# Boost_Converter.net
KiCad netlist of a schematic drawn in Altium Designer
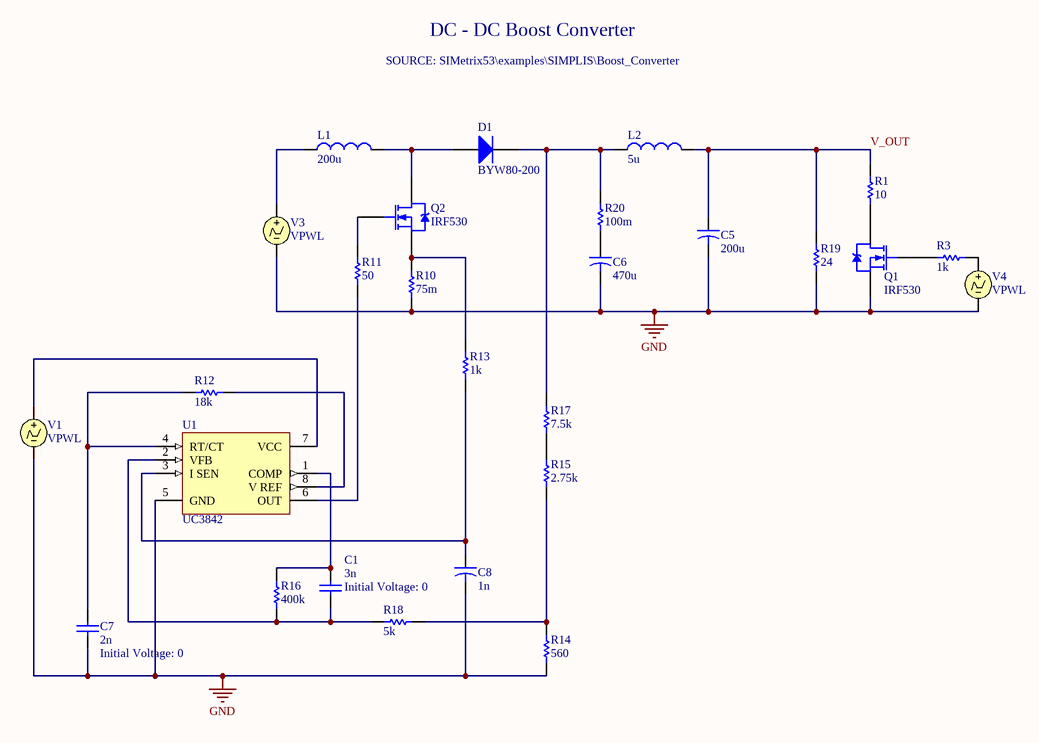
[diagram p0: Boost Converter.SchDoc]

(export (version "E")
  (design (tool "Eeschema 10.0.6"))
  (components
    (comp (ref "C1")
      (value "3n")
      (footprint "RAD-0.3")
      (description "Capacitor")
      (fields
        (field (name "INITIAL VOLTAGE") "0")
        (field (name "Comment") "Cap")
        (field (name "PUBLISHER") "Altium Limited")
      )
      (libsource (lib "Miscellaneous Devices") (part "Cap"))
    )
    (comp (ref "C5")
      (value "Cap Elec (L1-3)")
      (footprint "CAPR5-4X5")
      (description "Electrolytic Capacitor (Levels 1-3)")
      (fields (field (name "CC") "200u") (field (name "PUBLISHER") "Altium Limited"))
      (libsource (lib "SIMetrix Devices") (part "Cap Elec (L1-3)"))
    )
    (comp (ref "C6")
      (value "Cap Elec (L1-3)")
      (footprint "CAPR5-4X5")
      (description "Electrolytic Capacitor (Levels 1-3)")
      (fields (field (name "CC") "470u") (field (name "PUBLISHER") "Altium Limited"))
      (libsource (lib "SIMetrix Devices") (part "Cap Elec (L1-3)"))
    )
    (comp (ref "C7")
      (value "2n")
      (footprint "RAD-0.3")
      (description "Capacitor")
      (fields
        (field (name "INITIAL VOLTAGE") "0")
        (field (name "Comment") "Cap")
        (field (name "PUBLISHER") "Altium Limited")
      )
      (libsource (lib "Miscellaneous Devices") (part "Cap"))
    )
    (comp (ref "C8")
      (value "Cap Elec (L1-3)")
      (footprint "CAPR5-4X5")
      (description "Electrolytic Capacitor (Levels 1-3)")
      (fields (field (name "CC") "1n") (field (name "PUBLISHER") "Altium Limited"))
      (libsource (lib "SIMetrix Devices") (part "Cap Elec (L1-3)"))
    )
    (comp (ref "D1")
      (value "BYW80-200")
      (footprint "SMC")
      (description "High-Efficiency Fast Recovery Rectifier Diode")
      (fields (field (name "PUBLISHER") "Altium Limited"))
      (libsource (lib "SIMetrix Devices") (part "BYW80-200"))
    )
    (comp (ref "L1")
      (value "200u")
      (footprint "0402-A")
      (description "Lossy Inductor")
      (fields (field (name "PUBLISHER") "Altium Limited"))
      (libsource (lib "SIMetrix Devices") (part "Inductor (Lossy)"))
    )
    (comp (ref "L2")
      (value "5u")
      (footprint "0402-A")
      (description "Lossy Inductor")
      (fields (field (name "PUBLISHER") "Altium Limited"))
      (libsource (lib "SIMetrix Devices") (part "Inductor (Lossy)"))
    )
    (comp (ref "Q1")
      (value "IRF530")
      (footprint "TO-220AB")
      (description "HEXFET N-Channel Power MOSFET")
      (fields (field (name "PUBLISHER") "Altium Limited"))
      (libsource (lib "SIMetrix Devices") (part "IRF530"))
    )
    (comp (ref "Q2")
      (value "IRF530")
      (footprint "TO-220AB")
      (description "HEXFET N-Channel Power MOSFET")
      (fields (field (name "PUBLISHER") "Altium Limited"))
      (libsource (lib "SIMetrix Devices") (part "IRF530"))
    )
    (comp (ref "R1")
      (value "10")
      (footprint "AXIAL-0.3")
      (description "Resistor")
      (fields (field (name "Comment") "Res1") (field (name "PUBLISHER") "Altium Limited"))
      (libsource (lib "Miscellaneous Devices") (part "Res1"))
    )
    (comp (ref "R3")
      (value "1k")
      (footprint "AXIAL-0.3")
      (description "Resistor")
      (fields (field (name "Comment") "Res1") (field (name "PUBLISHER") "Altium Limited"))
      (libsource (lib "Miscellaneous Devices") (part "Res1"))
    )
    (comp (ref "R10")
      (value "75m")
      (footprint "AXIAL-0.3")
      (description "Resistor")
      (fields (field (name "Comment") "Res1") (field (name "PUBLISHER") "Altium Limited"))
      (libsource (lib "Miscellaneous Devices") (part "Res1"))
    )
    (comp (ref "R11")
      (value "50")
      (footprint "AXIAL-0.3")
      (description "Resistor")
      (fields (field (name "Comment") "Res1") (field (name "PUBLISHER") "Altium Limited"))
      (libsource (lib "Miscellaneous Devices") (part "Res1"))
    )
    (comp (ref "R12")
      (value "18k")
      (footprint "AXIAL-0.3")
      (description "Resistor")
      (fields (field (name "Comment") "Res1") (field (name "PUBLISHER") "Altium Limited"))
      (libsource (lib "Miscellaneous Devices") (part "Res1"))
    )
    (comp (ref "R13")
      (value "1k")
      (footprint "AXIAL-0.3")
      (description "Resistor")
      (fields (field (name "Comment") "Res1") (field (name "PUBLISHER") "Altium Limited"))
      (libsource (lib "Miscellaneous Devices") (part "Res1"))
    )
    (comp (ref "R14")
      (value "560")
      (footprint "AXIAL-0.3")
      (description "Resistor")
      (fields (field (name "Comment") "Res1") (field (name "PUBLISHER") "Altium Limited"))
      (libsource (lib "Miscellaneous Devices") (part "Res1"))
    )
    (comp (ref "R15")
      (value "2.75k")
      (footprint "AXIAL-0.3")
      (description "Resistor")
      (fields (field (name "Comment") "Res1") (field (name "PUBLISHER") "Altium Limited"))
      (libsource (lib "Miscellaneous Devices") (part "Res1"))
    )
    (comp (ref "R16")
      (value "400k")
      (footprint "AXIAL-0.3")
      (description "Resistor")
      (fields (field (name "Comment") "Res1") (field (name "PUBLISHER") "Altium Limited"))
      (libsource (lib "Miscellaneous Devices") (part "Res1"))
    )
    (comp (ref "R17")
      (value "7.5k")
      (footprint "AXIAL-0.3")
      (description "Resistor")
      (fields (field (name "Comment") "Res1") (field (name "PUBLISHER") "Altium Limited"))
      (libsource (lib "Miscellaneous Devices") (part "Res1"))
    )
    (comp (ref "R18")
      (value "5k")
      (footprint "AXIAL-0.3")
      (description "Resistor")
      (fields (field (name "Comment") "Res1") (field (name "PUBLISHER") "Altium Limited"))
      (libsource (lib "Miscellaneous Devices") (part "Res1"))
    )
    (comp (ref "R19")
      (value "24")
      (footprint "AXIAL-0.3")
      (description "Resistor")
      (fields (field (name "Comment") "Res1") (field (name "PUBLISHER") "Altium Limited"))
      (libsource (lib "Miscellaneous Devices") (part "Res1"))
    )
    (comp (ref "R20")
      (value "100m")
      (footprint "AXIAL-0.3")
      (description "Resistor")
      (fields (field (name "Comment") "Res1") (field (name "PUBLISHER") "Altium Limited"))
      (libsource (lib "Miscellaneous Devices") (part "Res1"))
    )
    (comp (ref "U1")
      (value "UC3842")
      (footprint "SO8_L")
      (description "High-Performance Current Mode PWM Controller")
      (fields (field (name "PUBLISHER") "Altium Limited"))
      (libsource (lib "SIMetrix Devices") (part "UC3842"))
    )
    (comp (ref "V1")
      (value "VPWL")
      (footprint "HDR1X2H")
      (description "Piecewise Linear Voltage Source")
      (fields (field (name "PUBLISHER") "Altium Limited"))
      (libsource (lib "Simulation Sources") (part "VPWL"))
    )
    (comp (ref "V3")
      (value "VPWL")
      (footprint "HDR1X2H")
      (description "Piecewise Linear Voltage Source")
      (fields (field (name "PUBLISHER") "Altium Limited"))
      (libsource (lib "Simulation Sources") (part "VPWL"))
    )
    (comp (ref "V4")
      (value "VPWL")
      (footprint "HDR1X2H")
      (description "Piecewise Linear Voltage Source")
      (fields (field (name "PUBLISHER") "Altium Limited"))
      (libsource (lib "Simulation Sources") (part "VPWL"))
    )
  )
  (nets
    (net (code "1") (name "/V_OUT") (class "Default")
      (node (ref "C5") (pin "1") (pinfunction "1_1") (pintype "passive"))
      (node (ref "L2") (pin "2") (pinfunction "2_2") (pintype "passive"))
      (node (ref "R1") (pin "1") (pinfunction "1_1") (pintype "passive"))
      (node (ref "R19") (pin "1") (pinfunction "1_1") (pintype "passive"))
    )
    (net (code "2") (name "GND") (class "Default")
      (node (ref "C5") (pin "2") (pinfunction "2_2") (pintype "passive"))
      (node (ref "C6") (pin "2") (pinfunction "2_2") (pintype "passive"))
      (node (ref "C7") (pin "2") (pinfunction "2_2") (pintype "passive"))
      (node (ref "C8") (pin "2") (pinfunction "2_2") (pintype "passive"))
      (node (ref "Q1") (pin "3") (pinfunction "S_3") (pintype "passive"))
      (node (ref "R10") (pin "1") (pinfunction "1_1") (pintype "passive"))
      (node (ref "R14") (pin "1") (pinfunction "1_1") (pintype "passive"))
      (node (ref "R19") (pin "2") (pinfunction "2_2") (pintype "passive"))
      (node (ref "U1") (pin "5") (pinfunction "GND_5") (pintype "power_in"))
      (node (ref "V1") (pin "2") (pinfunction "2_2") (pintype "passive"))
      (node (ref "V3") (pin "2") (pinfunction "2_2") (pintype "passive"))
      (node (ref "V4") (pin "2") (pinfunction "2_2") (pintype "passive"))
    )
    (net (code "3") (name "Net-(C6-Pad1)") (class "Default")
      (node (ref "C6") (pin "1") (pinfunction "1_1") (pintype "passive"))
      (node (ref "R20") (pin "1") (pinfunction "1_1") (pintype "passive"))
    )
    (net (code "4") (name "Net-(D1-A)") (class "Default")
      (node (ref "D1") (pin "1") (pinfunction "A_1") (pintype "passive"))
      (node (ref "L1") (pin "2") (pinfunction "2_2") (pintype "passive"))
      (node (ref "Q2") (pin "2") (pinfunction "D_2") (pintype "passive"))
    )
    (net (code "5") (name "Net-(D1-K)") (class "Default")
      (node (ref "D1") (pin "2") (pinfunction "K_2") (pintype "passive"))
      (node (ref "L2") (pin "1") (pinfunction "1_1") (pintype "passive"))
      (node (ref "R17") (pin "2") (pinfunction "2_2") (pintype "passive"))
      (node (ref "R20") (pin "2") (pinfunction "2_2") (pintype "passive"))
    )
    (net (code "6") (name "Net-(L1-Pad1)") (class "Default")
      (node (ref "L1") (pin "1") (pinfunction "1_1") (pintype "passive"))
      (node (ref "V3") (pin "1") (pinfunction "1_1") (pintype "passive"))
    )
    (net (code "7") (name "Net-(Q1-D)") (class "Default")
      (node (ref "Q1") (pin "2") (pinfunction "D_2") (pintype "passive"))
      (node (ref "R1") (pin "2") (pinfunction "2_2") (pintype "passive"))
    )
    (net (code "8") (name "Net-(Q1-G)") (class "Default")
      (node (ref "Q1") (pin "1") (pinfunction "G_1") (pintype "passive"))
      (node (ref "R3") (pin "1") (pinfunction "1_1") (pintype "passive"))
    )
    (net (code "9") (name "Net-(Q2-G)") (class "Default")
      (node (ref "Q2") (pin "1") (pinfunction "G_1") (pintype "passive"))
      (node (ref "R11") (pin "2") (pinfunction "2_2") (pintype "passive"))
    )
    (net (code "10") (name "Net-(Q2-S)") (class "Default")
      (node (ref "Q2") (pin "3") (pinfunction "S_3") (pintype "passive"))
      (node (ref "R10") (pin "2") (pinfunction "2_2") (pintype "passive"))
      (node (ref "R13") (pin "2") (pinfunction "2_2") (pintype "passive"))
    )
    (net (code "11") (name "Net-(R3-Pad2)") (class "Default")
      (node (ref "R3") (pin "2") (pinfunction "2_2") (pintype "passive"))
      (node (ref "V4") (pin "1") (pinfunction "1_1") (pintype "passive"))
    )
    (net (code "12") (name "Net-(R14-Pad2)") (class "Default")
      (node (ref "R14") (pin "2") (pinfunction "2_2") (pintype "passive"))
      (node (ref "R15") (pin "1") (pinfunction "1_1") (pintype "passive"))
      (node (ref "R18") (pin "1") (pinfunction "1_1") (pintype "passive"))
    )
    (net (code "13") (name "Net-(R15-Pad2)") (class "Default")
      (node (ref "R15") (pin "2") (pinfunction "2_2") (pintype "passive"))
      (node (ref "R17") (pin "1") (pinfunction "1_1") (pintype "passive"))
    )
    (net (code "14") (name "Net-(U1-COMP)") (class "Default")
      (node (ref "C1") (pin "1") (pinfunction "1_1") (pintype "passive"))
      (node (ref "R16") (pin "2") (pinfunction "2_2") (pintype "passive"))
      (node (ref "U1") (pin "1") (pinfunction "COMP_1") (pintype "output"))
    )
    (net (code "15") (name "Net-(U1-I_SEN)") (class "Default")
      (node (ref "C8") (pin "1") (pinfunction "1_1") (pintype "passive"))
      (node (ref "R13") (pin "1") (pinfunction "1_1") (pintype "passive"))
      (node (ref "U1") (pin "3") (pinfunction "I_SEN_3") (pintype "input"))
    )
    (net (code "16") (name "Net-(U1-OUT)") (class "Default")
      (node (ref "R11") (pin "1") (pinfunction "1_1") (pintype "passive"))
      (node (ref "U1") (pin "6") (pinfunction "OUT_6") (pintype "tri_state"))
    )
    (net (code "17") (name "Net-(U1-RT{slash}CT)") (class "Default")
      (node (ref "C7") (pin "1") (pinfunction "1_1") (pintype "passive"))
      (node (ref "R12") (pin "2") (pinfunction "2_2") (pintype "passive"))
      (node (ref "U1") (pin "4") (pinfunction "RT/CT_4") (pintype "input"))
    )
    (net (code "18") (name "Net-(U1-VCC)") (class "Default")
      (node (ref "U1") (pin "7") (pinfunction "VCC_7") (pintype "power_in"))
      (node (ref "V1") (pin "1") (pinfunction "1_1") (pintype "passive"))
    )
    (net (code "19") (name "Net-(U1-VFB)") (class "Default")
      (node (ref "C1") (pin "2") (pinfunction "2_2") (pintype "passive"))
      (node (ref "R16") (pin "1") (pinfunction "1_1") (pintype "passive"))
      (node (ref "R18") (pin "2") (pinfunction "2_2") (pintype "passive"))
      (node (ref "U1") (pin "2") (pinfunction "VFB_2") (pintype "input"))
    )
    (net (code "20") (name "Net-(U1-V_REF)") (class "Default")
      (node (ref "R12") (pin "1") (pinfunction "1_1") (pintype "passive"))
      (node (ref "U1") (pin "8") (pinfunction "V_REF_8") (pintype "output"))
    )
  )
)
